# BlinkingLEDs.net
KiCad netlist of a schematic drawn in EAGLE
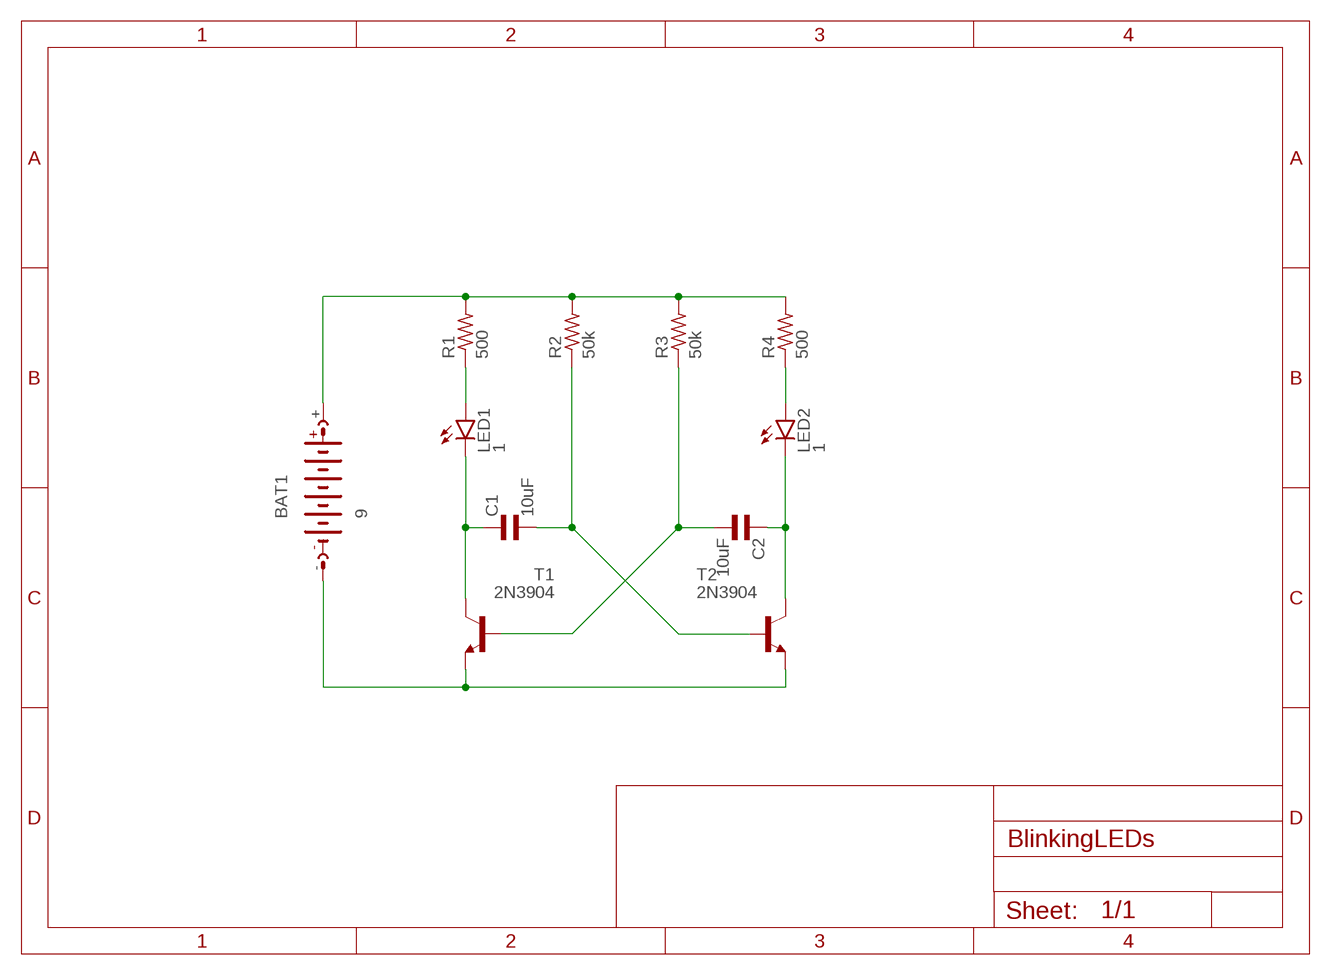
[diagram p0: schematic, sheet 1]

(export (version "E")
  (design (tool "Eeschema 10.0.6"))
  (components
    (comp (ref "BAT1")
      (value "9")
      (footprint "eagle-import:AB9V")
      (libsource (lib "eagle-import") (part "AB9V"))
    )
    (comp (ref "C1")
      (value "10uF")
      (footprint "eagle-import:EU25-10")
      (libsource (lib "eagle-import") (part "EL-BI25-10AXIAL"))
    )
    (comp (ref "C2")
      (value "10uF")
      (footprint "eagle-import:EU25-10")
      (libsource (lib "eagle-import") (part "EL-BI25-10AXIAL"))
    )
    (comp (ref "LED1")
      (value "1")
      (footprint "eagle-import:LED5MM")
      (libsource (lib "eagle-import") (part "LED5MM"))
    )
    (comp (ref "LED2")
      (value "1")
      (footprint "eagle-import:LED5MM")
      (libsource (lib "eagle-import") (part "LED5MM"))
    )
    (comp (ref "R1")
      (value "500")
      (footprint "eagle-import:0204_7")
      (libsource (lib "eagle-import") (part "R-US_0204/7"))
    )
    (comp (ref "R2")
      (value "50k")
      (footprint "eagle-import:0204_7")
      (libsource (lib "eagle-import") (part "R-US_0204/7"))
    )
    (comp (ref "R3")
      (value "50k")
      (footprint "eagle-import:0204_7")
      (libsource (lib "eagle-import") (part "R-US_0204/7"))
    )
    (comp (ref "R4")
      (value "500")
      (footprint "eagle-import:0204_7")
      (libsource (lib "eagle-import") (part "R-US_0204/7"))
    )
    (comp (ref "T1")
      (value "2N3904")
      (footprint "eagle-import:TO92")
      (libsource (lib "eagle-import") (part "2N3904"))
    )
    (comp (ref "T2")
      (value "2N3904")
      (footprint "eagle-import:TO92")
      (libsource (lib "eagle-import") (part "2N3904"))
    )
  )
  (nets
    (net (code "1") (name "Net-(BAT1-Pad+)") (class "Default")
      (node (ref "BAT1") (pin "+") (pinfunction "+_+") (pintype "passive"))
      (node (ref "R1") (pin "2") (pinfunction "2_2") (pintype "passive"))
      (node (ref "R2") (pin "2") (pinfunction "2_2") (pintype "passive"))
      (node (ref "R3") (pin "2") (pinfunction "2_2") (pintype "passive"))
      (node (ref "R4") (pin "2") (pinfunction "2_2") (pintype "passive"))
    )
    (net (code "2") (name "Net-(LED1-C)") (class "Default")
      (node (ref "C1") (pin "1") (pinfunction "1_1") (pintype "passive"))
      (node (ref "LED1") (pin "K") (pinfunction "C_K") (pintype "passive"))
      (node (ref "T1") (pin "1") (pinfunction "C_1") (pintype "passive"))
    )
    (net (code "3") (name "Net-(LED1-PadA)") (class "Default")
      (node (ref "LED1") (pin "A") (pinfunction "A_A") (pintype "passive"))
      (node (ref "R1") (pin "1") (pinfunction "1_1") (pintype "passive"))
    )
    (net (code "4") (name "Net-(LED2-C)") (class "Default")
      (node (ref "C2") (pin "1") (pinfunction "1_1") (pintype "passive"))
      (node (ref "LED2") (pin "K") (pinfunction "C_K") (pintype "passive"))
      (node (ref "T2") (pin "1") (pinfunction "C_1") (pintype "passive"))
    )
    (net (code "5") (name "Net-(LED2-PadA)") (class "Default")
      (node (ref "LED2") (pin "A") (pinfunction "A_A") (pintype "passive"))
      (node (ref "R4") (pin "1") (pinfunction "1_1") (pintype "passive"))
    )
    (net (code "6") (name "Net-(T1-B)") (class "Default")
      (node (ref "C2") (pin "2") (pinfunction "2_2") (pintype "passive"))
      (node (ref "R3") (pin "1") (pinfunction "1_1") (pintype "passive"))
      (node (ref "T1") (pin "2") (pinfunction "B_2") (pintype "passive"))
    )
    (net (code "7") (name "Net-(T1-E)") (class "Default")
      (node (ref "BAT1") (pin "-") (pinfunction "-_-") (pintype "passive"))
      (node (ref "T1") (pin "3") (pinfunction "E_3") (pintype "passive"))
      (node (ref "T2") (pin "3") (pinfunction "E_3") (pintype "passive"))
    )
    (net (code "8") (name "Net-(T2-B)") (class "Default")
      (node (ref "C1") (pin "2") (pinfunction "2_2") (pintype "passive"))
      (node (ref "R2") (pin "1") (pinfunction "1_1") (pintype "passive"))
      (node (ref "T2") (pin "2") (pinfunction "B_2") (pintype "passive"))
    )
  )
)
